# STM32RF_NRF.net
KiCad netlist of a schematic drawn in Altium Designer
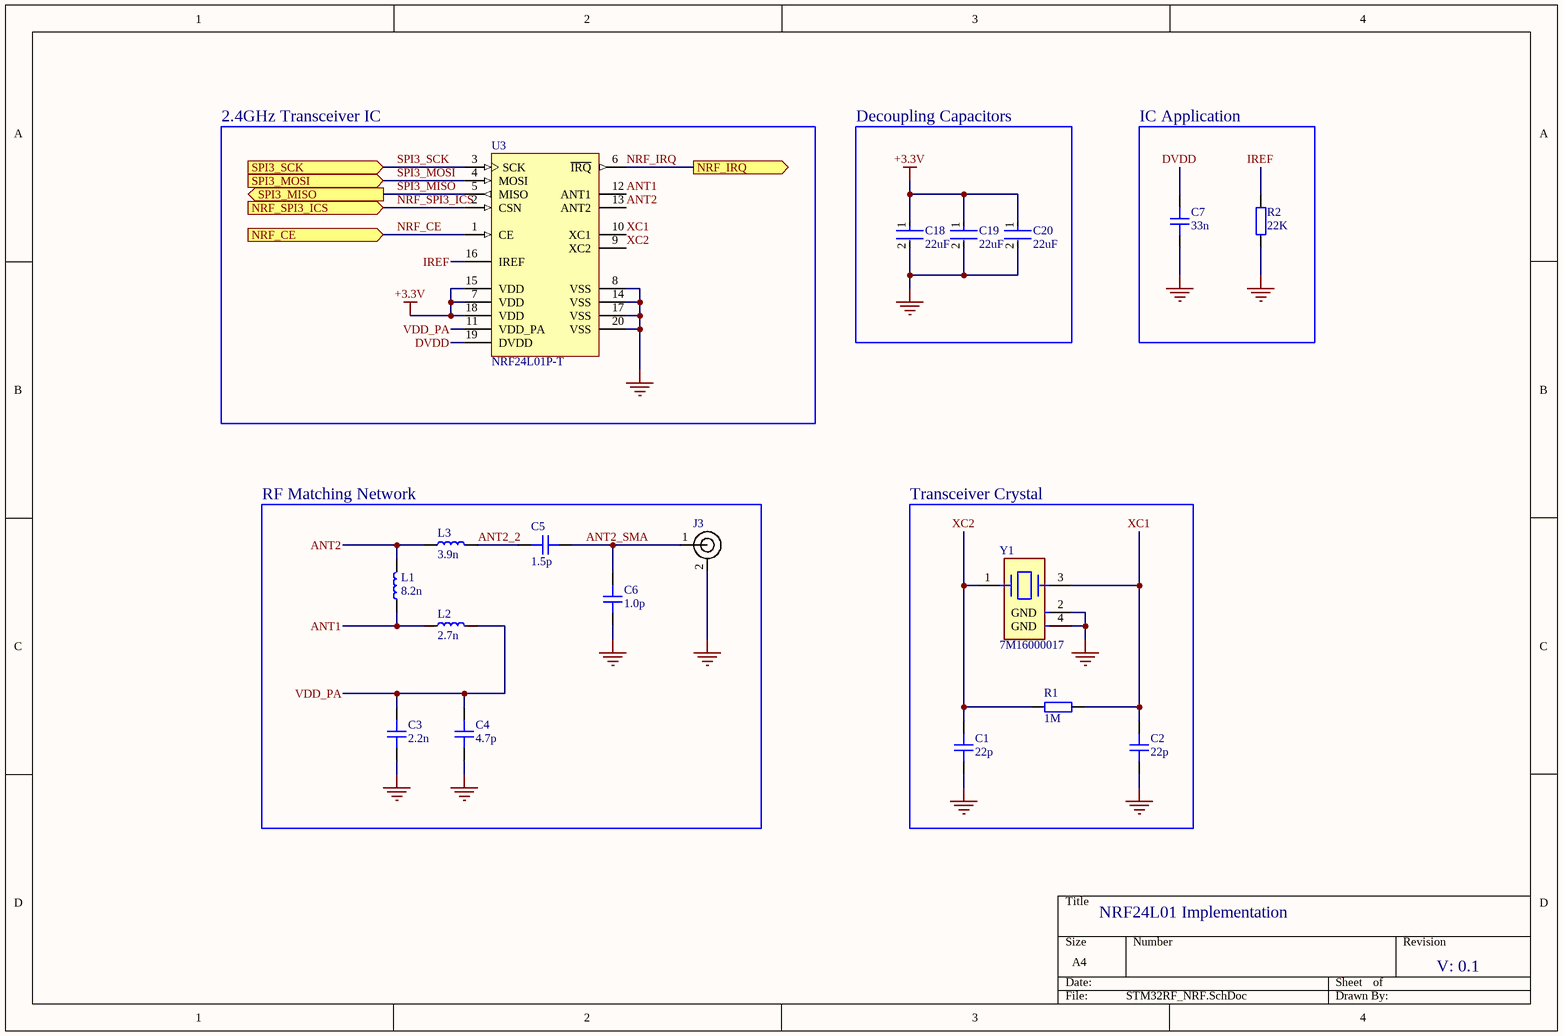
[diagram p0: STM32RF_NRF.SchDoc]

(export (version "E")
  (design (tool "Eeschema 10.0.6"))
  (components
    (comp (ref "C1")
      (value "22p")
      (footprint "CAP_0402")
      (description "Capacitor SMD 0402")
      (libsource (lib "Schematic-Lib-PhilsLab") (part "CAP_0402"))
    )
    (comp (ref "C2")
      (value "22p")
      (footprint "CAP_0402")
      (description "Capacitor SMD 0402")
      (libsource (lib "Schematic-Lib-PhilsLab") (part "CAP_0402"))
    )
    (comp (ref "C3")
      (value "2.2n")
      (footprint "CAP_0402")
      (description "Capacitor SMD 0402")
      (libsource (lib "Schematic-Lib-PhilsLab") (part "CAP_0402"))
    )
    (comp (ref "C4")
      (value "4.7p")
      (footprint "CAP_0402")
      (description "Capacitor SMD 0402")
      (libsource (lib "Schematic-Lib-PhilsLab") (part "CAP_0402"))
    )
    (comp (ref "C5")
      (value "1.5p")
      (footprint "CAP_0402")
      (description "Capacitor SMD 0402")
      (libsource (lib "Schematic-Lib-PhilsLab") (part "CAP_0402"))
    )
    (comp (ref "C6")
      (value "1.0p")
      (footprint "CAP_0402")
      (description "Capacitor SMD 0402")
      (libsource (lib "Schematic-Lib-PhilsLab") (part "CAP_0402"))
    )
    (comp (ref "C7")
      (value "33n")
      (footprint "CAP_0402")
      (description "Capacitor SMD 0402")
      (libsource (lib "Schematic-Lib-PhilsLab") (part "CAP_0402"))
    )
    (comp (ref "C18")
      (value "22uF")
      (footprint "FP-GRM158-0_2-MFG")
      (description "Chip Multilayer Ceramic Capacitors for General Purpose, 0402, 22uF, X5R, 15%, 20%, 10V")
      (libsource (lib "Altium Content Vault") (part "b4654b650e69147ec39a6b967a45e02"))
    )
    (comp (ref "C19")
      (value "22uF")
      (footprint "FP-GRM158-0_2-MFG")
      (description "Chip Multilayer Ceramic Capacitors for General Purpose, 0402, 22uF, X5R, 15%, 20%, 10V")
      (libsource (lib "Altium Content Vault") (part "b4654b650e69147ec39a6b967a45e02"))
    )
    (comp (ref "C20")
      (value "22uF")
      (footprint "FP-GRM158-0_2-MFG")
      (description "Chip Multilayer Ceramic Capacitors for General Purpose, 0402, 22uF, X5R, 15%, 20%, 10V")
      (libsource (lib "Altium Content Vault") (part "b4654b650e69147ec39a6b967a45e02"))
    )
    (comp (ref "J3")
      (value "CON-SMA-EDGE-S")
      (footprint "CON-SMA-EDGE-S")
      (description "RF Connector SMA Female 50 Ohms 18 GHz PCB Edge Mount")
      (fields (field (name "MANUFACTURER") "RF Solutions"))
      (libsource (lib "Schematic-Lib-PhilsLab") (part "CON-SMA-EDGE-S"))
    )
    (comp (ref "L1")
      (value "8.2n")
      (footprint "IND_0402")
      (description "Inductor SMD 0402")
      (libsource (lib "Schematic-Lib-PhilsLab") (part "IND_0402"))
    )
    (comp (ref "L2")
      (value "2.7n")
      (footprint "IND_0402")
      (description "Inductor SMD 0402")
      (libsource (lib "Schematic-Lib-PhilsLab") (part "IND_0402"))
    )
    (comp (ref "L3")
      (value "3.9n")
      (footprint "IND_0402")
      (description "Inductor SMD 0402")
      (libsource (lib "Schematic-Lib-PhilsLab") (part "IND_0402"))
    )
    (comp (ref "R1")
      (value "1M")
      (footprint "RES_0402")
      (description "Resistor SMD 0402")
      (libsource (lib "Schematic-Lib-PhilsLab") (part "RES_0402"))
    )
    (comp (ref "R2")
      (value "22K")
      (footprint "RES_0402")
      (description "Resistor SMD 0402")
      (libsource (lib "Schematic-Lib-PhilsLab") (part "RES_0402"))
    )
    (comp (ref "U3")
      (value "NRF24L01P-T")
      (footprint "NRSC-QFN-20_L")
      (description "Single Chip Transceiver, 2.4 GHz, 60 mW, 1.9 to 3.6 V, -40 to 85 degC, 20-Pin QFN, RoHS, Tray")
      (fields (field (name "MANUFACTURER") "Nordic Semiconductor"))
      (libsource (lib "Altium Content Vault") (part "NRSC-NRF24L01P-QFN-20"))
    )
    (comp (ref "Y1")
      (value "7M16000017")
      (footprint "FP-7M-MFG")
      (description "Crystal 16MHz, 10ppm, 9pF, 60Ω")
      (libsource (lib "Altium Content Vault") (part "41079aabb0e87794b56622915be14ed"))
    )
  )
  (nets
    (net (code "1") (name "+3.3V") (class "Default")
      (node (ref "C18") (pin "1") (pinfunction "1_1") (pintype "passive"))
      (node (ref "C19") (pin "1") (pinfunction "1_1") (pintype "passive"))
      (node (ref "C20") (pin "1") (pinfunction "1_1") (pintype "passive"))
      (node (ref "U3") (pin "15") (pinfunction "VDD_15") (pintype "power_in"))
      (node (ref "U3") (pin "18") (pinfunction "VDD_18") (pintype "power_in"))
      (node (ref "U3") (pin "7") (pinfunction "VDD_7") (pintype "power_in"))
    )
    (net (code "2") (name "/ANT1") (class "Default")
      (node (ref "L1") (pin "1") (pinfunction "1_1") (pintype "passive"))
      (node (ref "L2") (pin "1") (pinfunction "1_1") (pintype "passive"))
      (node (ref "U3") (pin "12") (pinfunction "ANT1_12") (pintype "passive"))
    )
    (net (code "3") (name "/ANT2") (class "Default")
      (node (ref "L1") (pin "2") (pinfunction "2_2") (pintype "passive"))
      (node (ref "L3") (pin "1") (pinfunction "1_1") (pintype "passive"))
      (node (ref "U3") (pin "13") (pinfunction "ANT2_13") (pintype "passive"))
    )
    (net (code "4") (name "/ANT2_2") (class "Default")
      (node (ref "C5") (pin "2") (pinfunction "2_2") (pintype "passive"))
      (node (ref "L3") (pin "2") (pinfunction "2_2") (pintype "passive"))
    )
    (net (code "5") (name "/ANT2_SMA") (class "Default")
      (node (ref "C5") (pin "1") (pinfunction "1_1") (pintype "passive"))
      (node (ref "C6") (pin "2") (pinfunction "2_2") (pintype "passive"))
      (node (ref "J3") (pin "1") (pinfunction "1_1") (pintype "passive"))
    )
    (net (code "6") (name "/DVDD") (class "Default")
      (node (ref "C7") (pin "2") (pinfunction "2_2") (pintype "passive"))
      (node (ref "U3") (pin "19") (pinfunction "DVDD_19") (pintype "power_in"))
    )
    (net (code "7") (name "/IREF") (class "Default")
      (node (ref "R2") (pin "2") (pinfunction "2_2") (pintype "passive"))
      (node (ref "U3") (pin "16") (pinfunction "IREF_16") (pintype "passive"))
    )
    (net (code "8") (name "/NRF_CE") (class "Default")
      (node (ref "U3") (pin "1") (pinfunction "CE_1") (pintype "input"))
    )
    (net (code "9") (name "/NRF_IRQ") (class "Default")
      (node (ref "U3") (pin "6") (pinfunction "~{IRQ}_6") (pintype "output"))
    )
    (net (code "10") (name "/NRF_SPI3_ICS") (class "Default")
      (node (ref "U3") (pin "2") (pinfunction "CSN_2") (pintype "input"))
    )
    (net (code "11") (name "/SPI3_MISO") (class "Default")
      (node (ref "U3") (pin "5") (pinfunction "MISO_5") (pintype "output"))
    )
    (net (code "12") (name "/SPI3_MOSI") (class "Default")
      (node (ref "U3") (pin "4") (pinfunction "MOSI_4") (pintype "input"))
    )
    (net (code "13") (name "/SPI3_SCK") (class "Default")
      (node (ref "U3") (pin "3") (pinfunction "SCK_3") (pintype "input"))
    )
    (net (code "14") (name "/VDD_PA") (class "Default")
      (node (ref "C3") (pin "2") (pinfunction "2_2") (pintype "passive"))
      (node (ref "C4") (pin "2") (pinfunction "2_2") (pintype "passive"))
      (node (ref "L2") (pin "2") (pinfunction "2_2") (pintype "passive"))
      (node (ref "U3") (pin "11") (pinfunction "VDD_PA_11") (pintype "power_in"))
    )
    (net (code "15") (name "/XC1") (class "Default")
      (node (ref "C2") (pin "2") (pinfunction "2_2") (pintype "passive"))
      (node (ref "R1") (pin "2") (pinfunction "2_2") (pintype "passive"))
      (node (ref "U3") (pin "10") (pinfunction "XC1_10") (pintype "passive"))
      (node (ref "Y1") (pin "3") (pinfunction "3_3") (pintype "passive"))
    )
    (net (code "16") (name "/XC2") (class "Default")
      (node (ref "C1") (pin "2") (pinfunction "2_2") (pintype "passive"))
      (node (ref "R1") (pin "1") (pinfunction "1_1") (pintype "passive"))
      (node (ref "U3") (pin "9") (pinfunction "XC2_9") (pintype "passive"))
      (node (ref "Y1") (pin "1") (pinfunction "1_1") (pintype "passive"))
    )
    (net (code "17") (name "GND") (class "Default")
      (node (ref "C1") (pin "1") (pinfunction "1_1") (pintype "passive"))
      (node (ref "C18") (pin "2") (pinfunction "2_2") (pintype "passive"))
      (node (ref "C19") (pin "2") (pinfunction "2_2") (pintype "passive"))
      (node (ref "C2") (pin "1") (pinfunction "1_1") (pintype "passive"))
      (node (ref "C20") (pin "2") (pinfunction "2_2") (pintype "passive"))
      (node (ref "C3") (pin "1") (pinfunction "1_1") (pintype "passive"))
      (node (ref "C4") (pin "1") (pinfunction "1_1") (pintype "passive"))
      (node (ref "C6") (pin "1") (pinfunction "1_1") (pintype "passive"))
      (node (ref "C7") (pin "1") (pinfunction "1_1") (pintype "passive"))
      (node (ref "J3") (pin "2") (pinfunction "2_2") (pintype "passive"))
      (node (ref "R2") (pin "1") (pinfunction "1_1") (pintype "passive"))
      (node (ref "U3") (pin "14") (pinfunction "VSS_14") (pintype "power_in"))
      (node (ref "U3") (pin "17") (pinfunction "VSS_17") (pintype "power_in"))
      (node (ref "U3") (pin "20") (pinfunction "VSS_20") (pintype "power_in"))
      (node (ref "U3") (pin "8") (pinfunction "VSS_8") (pintype "power_in"))
      (node (ref "Y1") (pin "2") (pinfunction "GND_2") (pintype "power_in"))
      (node (ref "Y1") (pin "4") (pinfunction "GND_4") (pintype "power_in"))
    )
  )
)
